# LEDBAKL_MP3202_AP3032.net
KiCad netlist of a schematic drawn in Altium Designer
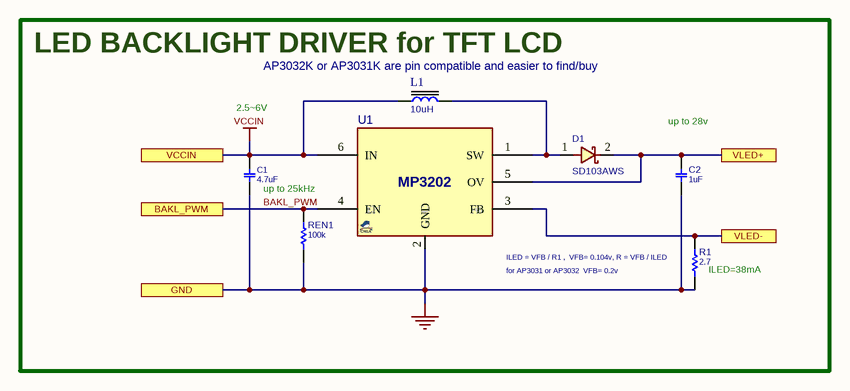
[diagram p0: LEDBAKL_MP3202_AP3032.SchDoc]

(export (version "E")
  (design (tool "Eeschema 10.0.6"))
  (components
    (comp (ref "C1")
      (value "4.7uF")
      (footprint "C0402")
      (description "CAP, MLCC")
      (fields (field (name "MANF_P#") "CL05A475MP5NRNC") (field (name "MANF") "Samsung"))
      (libsource (lib "passive_smd") (part "CAP_SMD_MLCC"))
    )
    (comp (ref "C2")
      (value "1uF")
      (footprint "C0603")
      (description "CAP, MLCC")
      (fields (field (name "MANF_P#") "CL10A105KB8NNNC") (field (name "MANF") "Samsung"))
      (libsource (lib "passive_smd") (part "CAP_SMD_MLCC"))
    )
    (comp (ref "D1")
      (value "SD103AWS")
      (footprint "D_SOD323")
      (description "DIODE, SCHOTTKY, 40V, 2A")
      (fields (field (name "MANF") "DIODES"))
      (libsource (lib "diode") (part "DIODE_SMD_SCHOTTKY_1N5819"))
    )
    (comp (ref "L1")
      (value "10uH")
      (footprint "L_4")
      (description "INDUCTOR, POWER, SMD")
      (fields (field (name "MANF_P#") "GCD43-100MC"))
      (libsource (lib "passive") (part "INDPWR_SMD"))
    )
    (comp (ref "R1")
      (value "2.7")
      (footprint "R0402")
      (description "RESISTOR, SMD, 20K, 0402")
      (fields (field (name "MANF") "Yageo") (field (name "MANF_P#") "RK73H1ETTP2002F"))
      (libsource (lib "chila_passive") (part "RES_SMD"))
    )
    (comp (ref "REN1")
      (value "100k")
      (footprint "R0402")
      (description "RESISTOR, SMD, 20K, 0402")
      (fields (field (name "MANF") "Yageo") (field (name "MANF_P#") "RK73H1ETTP2002F"))
      (libsource (lib "chila_passive") (part "RES_SMD"))
    )
    (comp (ref "U1")
      (value "MP3202")
      (footprint "SOT23_6")
      (description "REG, Switching, Boost, 1.3A, ADJ, 1MHz, SOT-23-6")
      (fields (field (name "MANF_P#") "MP3202DJ") (field (name "MANF") "MPS"))
      (libsource (lib "pwr_switching_boost") (part "VREG_MP3202_SOT23"))
    )
  )
  (nets
    (net (code "1") (name "/BAKL_PWM") (class "Default")
      (node (ref "REN1") (pin "1") (pinfunction "1_1") (pintype "passive"))
      (node (ref "U1") (pin "4") (pinfunction "EN_4") (pintype "passive"))
    )
    (net (code "2") (name "/VLED+") (class "Default")
      (node (ref "C2") (pin "2") (pinfunction "2_2") (pintype "passive"))
      (node (ref "D1") (pin "2") (pinfunction "2_2") (pintype "passive"))
      (node (ref "U1") (pin "5") (pinfunction "OV_5") (pintype "passive"))
    )
    (net (code "3") (name "/VLED-") (class "Default")
      (node (ref "R1") (pin "1") (pinfunction "1_1") (pintype "passive"))
      (node (ref "U1") (pin "3") (pinfunction "FB_3") (pintype "passive"))
    )
    (net (code "4") (name "GND") (class "Default")
      (node (ref "C1") (pin "1") (pinfunction "1_1") (pintype "passive"))
      (node (ref "C2") (pin "1") (pinfunction "1_1") (pintype "passive"))
      (node (ref "R1") (pin "2") (pinfunction "2_2") (pintype "passive"))
      (node (ref "REN1") (pin "2") (pinfunction "2_2") (pintype "passive"))
      (node (ref "U1") (pin "2") (pinfunction "GND_2") (pintype "tri_state"))
    )
    (net (code "5") (name "Net-(U1-SW)") (class "Default")
      (node (ref "D1") (pin "1") (pinfunction "1_1") (pintype "passive"))
      (node (ref "L1") (pin "2") (pinfunction "2_2") (pintype "passive"))
      (node (ref "U1") (pin "1") (pinfunction "SW_1") (pintype "passive"))
    )
    (net (code "6") (name "VCCIN") (class "Default")
      (node (ref "C1") (pin "2") (pinfunction "2_2") (pintype "passive"))
      (node (ref "L1") (pin "1") (pinfunction "1_1") (pintype "passive"))
      (node (ref "U1") (pin "6") (pinfunction "IN_6") (pintype "passive"))
    )
  )
)
